# attack_board.net
KiCad netlist of a schematic drawn in Altium Designer
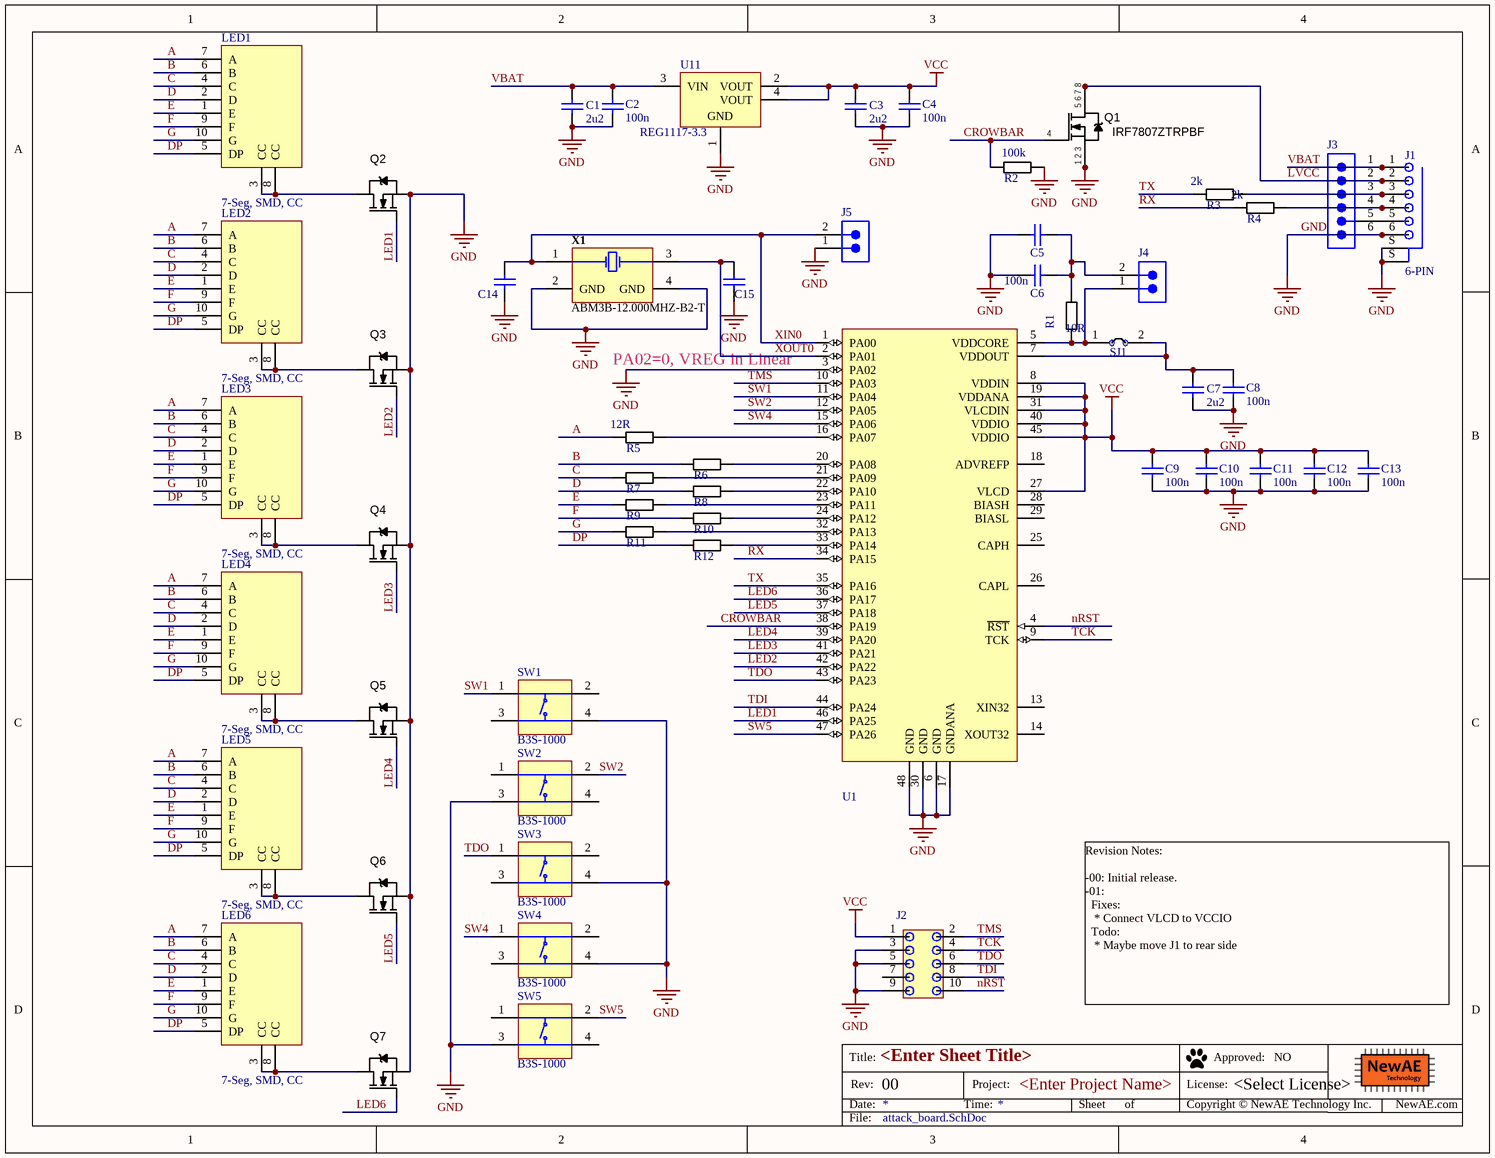
[diagram p0: attack_board.SchDoc]

(export (version "E")
  (design (tool "Eeschema 10.0.6"))
  (components
    (comp (ref "C1")
      (value "2u2")
      (footprint "CAPC0603_M")
      (description "2u2, 0603")
      (fields (field (name "PART NUMBER") "CCHIP-2u2-0603"))
      (libsource (lib "NewAE_AltiumLib") (part "CAP"))
    )
    (comp (ref "C2")
      (value "100n")
      (footprint "CAPC0603_M")
      (description "100n, 0603")
      (fields (field (name "PART NUMBER") "CCHIP-100n-0603"))
      (libsource (lib "NewAE_AltiumLib") (part "CAP"))
    )
    (comp (ref "C3")
      (value "2u2")
      (footprint "CAPC0603_M")
      (description "2u2, 0603")
      (fields (field (name "PART NUMBER") "CCHIP-2u2-0603"))
      (libsource (lib "NewAE_AltiumLib") (part "CAP"))
    )
    (comp (ref "C4")
      (value "100n")
      (footprint "CAPC0603_M")
      (description "100n, 0603")
      (fields (field (name "PART NUMBER") "CCHIP-100n-0603"))
      (libsource (lib "NewAE_AltiumLib") (part "CAP"))
    )
    (comp (ref "C5")
      (value "2u2")
      (footprint "CAPC0603_M")
      (description "2u2, 0603")
      (fields (field (name "PART NUMBER") "CCHIP-2u2-0603"))
      (libsource (lib "NewAE_AltiumLib") (part "CAP"))
    )
    (comp (ref "C6")
      (value "100n")
      (footprint "CAPC0603_M")
      (description "100n, 0603")
      (fields (field (name "PART NUMBER") "CCHIP-100n-0603"))
      (libsource (lib "NewAE_AltiumLib") (part "CAP"))
    )
    (comp (ref "C7")
      (value "2u2")
      (footprint "CAPC0603_M")
      (description "2u2, 0603")
      (fields (field (name "PART NUMBER") "CCHIP-2u2-0603"))
      (libsource (lib "NewAE_AltiumLib") (part "CAP"))
    )
    (comp (ref "C8")
      (value "100n")
      (footprint "CAPC0603_M")
      (description "100n, 0603")
      (fields (field (name "PART NUMBER") "CCHIP-100n-0603"))
      (libsource (lib "NewAE_AltiumLib") (part "CAP"))
    )
    (comp (ref "C9")
      (value "100n")
      (footprint "CAPC0603_M")
      (description "100n, 0603")
      (fields (field (name "PART NUMBER") "CCHIP-100n-0603"))
      (libsource (lib "NewAE_AltiumLib") (part "CAP"))
    )
    (comp (ref "C10")
      (value "100n")
      (footprint "CAPC0603_M")
      (description "100n, 0603")
      (fields (field (name "PART NUMBER") "CCHIP-100n-0603"))
      (libsource (lib "NewAE_AltiumLib") (part "CAP"))
    )
    (comp (ref "C11")
      (value "100n")
      (footprint "CAPC0603_M")
      (description "100n, 0603")
      (fields (field (name "PART NUMBER") "CCHIP-100n-0603"))
      (libsource (lib "NewAE_AltiumLib") (part "CAP"))
    )
    (comp (ref "C12")
      (value "100n")
      (footprint "CAPC0603_M")
      (description "100n, 0603")
      (fields (field (name "PART NUMBER") "CCHIP-100n-0603"))
      (libsource (lib "NewAE_AltiumLib") (part "CAP"))
    )
    (comp (ref "C13")
      (value "100n")
      (footprint "CAPC0603_M")
      (description "100n, 0603")
      (fields (field (name "PART NUMBER") "CCHIP-100n-0603"))
      (libsource (lib "NewAE_AltiumLib") (part "CAP"))
    )
    (comp (ref "C14")
      (value "18p")
      (footprint "CAPC0402_M")
      (description "18p, 0402")
      (fields (field (name "PART NUMBER") "CCHIP-18p-0402"))
      (libsource (lib "NewAE_AltiumLib") (part "CAP"))
    )
    (comp (ref "C15")
      (value "18p")
      (footprint "CAPC0402_M")
      (description "18p, 0402")
      (fields (field (name "PART NUMBER") "CCHIP-18p-0402"))
      (libsource (lib "NewAE_AltiumLib") (part "CAP"))
    )
    (comp (ref "J1")
      (value "6-PIN")
      (footprint "10114828-10106LF")
      (description "1.25MM, 6POS, VERT SMD")
      (fields (field (name "PART NUMBER") "10114828-10106LF"))
      (libsource (lib "NewAE_AltiumLib") (part "CON6_2MNT"))
    )
    (comp (ref "J2")
      (value "1296-T10")
      (footprint "1296-T10")
      (description "Header, 10-pin, SMD, 0.05\"")
      (libsource (lib "NewAE_AltiumLib") (part "CON10_2ROW"))
    )
    (comp (ref "J3")
      (value "~")
      (footprint "SMTC-TSW-106-08-X-S-RA")
      (fields (field (name "PARTNUMBER") "TSW-106-08-T-S-RA") (field (name "MANUFACTURER") "Samtec"))
      (libsource (lib "Altium Content Vault") (part "CMP-1024-00388-1"))
    )
    (comp (ref "J4")
      (value "~")
      (footprint "SMTC-DW-02-16-X-S-200")
      (fields (field (name "PARTNUMBER") "DW-02-16-G-S-200") (field (name "MANUFACTURER") "Samtec"))
      (libsource (lib "Altium Content Vault") (part "CMP-1024-00001-1"))
    )
    (comp (ref "J5")
      (value "~")
      (footprint "SMTC-DW-02-16-X-S-200")
      (fields (field (name "PARTNUMBER") "DW-02-16-G-S-200") (field (name "MANUFACTURER") "Samtec"))
      (libsource (lib "Altium Content Vault") (part "CMP-1024-00001-1"))
    )
    (comp (ref "LED1")
      (value "7-Seg, SMD, CC")
      (description "7-Seg, CC")
      (libsource (lib "NewAE_AltiumLib") (part "ACSC03"))
    )
    (comp (ref "LED2")
      (value "7-Seg, SMD, CC")
      (description "7-Seg, CC")
      (libsource (lib "NewAE_AltiumLib") (part "ACSC03"))
    )
    (comp (ref "LED3")
      (value "7-Seg, SMD, CC")
      (description "7-Seg, CC")
      (libsource (lib "NewAE_AltiumLib") (part "ACSC03"))
    )
    (comp (ref "LED4")
      (value "7-Seg, SMD, CC")
      (description "7-Seg, CC")
      (libsource (lib "NewAE_AltiumLib") (part "ACSC03"))
    )
    (comp (ref "LED5")
      (value "7-Seg, SMD, CC")
      (description "7-Seg, CC")
      (libsource (lib "NewAE_AltiumLib") (part "ACSC03"))
    )
    (comp (ref "LED6")
      (value "7-Seg, SMD, CC")
      (description "7-Seg, CC")
      (libsource (lib "NewAE_AltiumLib") (part "ACSC03"))
    )
    (comp (ref "Q1")
      (value "IRF7807ZTRPBF")
      (footprint "SOIC8_NARROW")
      (description "MOSFET, N-Channel, 8-SOIC, Logic Level")
      (libsource (lib "NewAE_AltiumLib") (part "MOSFET_NCH_8SOIC"))
    )
    (comp (ref "Q2")
      (value "IRLML2502")
      (footprint "SOT95P245X110-3M")
      (description "MOSFET, N-Channel, SOT23, Logic Level")
      (libsource (lib "NewAE_AltiumLib") (part "MOSFET_N_GSD"))
    )
    (comp (ref "Q3")
      (value "IRLML2502")
      (footprint "SOT95P245X110-3M")
      (description "MOSFET, N-Channel, SOT23, Logic Level")
      (libsource (lib "NewAE_AltiumLib") (part "MOSFET_N_GSD"))
    )
    (comp (ref "Q4")
      (value "IRLML2502")
      (footprint "SOT95P245X110-3M")
      (description "MOSFET, N-Channel, SOT23, Logic Level")
      (libsource (lib "NewAE_AltiumLib") (part "MOSFET_N_GSD"))
    )
    (comp (ref "Q5")
      (value "IRLML2502")
      (footprint "SOT95P245X110-3M")
      (description "MOSFET, N-Channel, SOT23, Logic Level")
      (libsource (lib "NewAE_AltiumLib") (part "MOSFET_N_GSD"))
    )
    (comp (ref "Q6")
      (value "IRLML2502")
      (footprint "SOT95P245X110-3M")
      (description "MOSFET, N-Channel, SOT23, Logic Level")
      (libsource (lib "NewAE_AltiumLib") (part "MOSFET_N_GSD"))
    )
    (comp (ref "Q7")
      (value "IRLML2502")
      (footprint "SOT95P245X110-3M")
      (description "MOSFET, N-Channel, SOT23, Logic Level")
      (libsource (lib "NewAE_AltiumLib") (part "MOSFET_N_GSD"))
    )
    (comp (ref "R1")
      (value "10R")
      (footprint "RESC1608X55N")
      (description "10R res, 0603, 1%, 1/10W")
      (fields (field (name "PART NUMBER") "RCHIP-10R-0603") (field (name "TOLERANCE") "1%"))
      (libsource (lib "") (part "RES-EU_1"))
    )
    (comp (ref "R2")
      (value "100k")
      (footprint "RESC1608X55N")
      (description "100k res, 0603, 1%, 1/10W")
      (fields (field (name "PART NUMBER") "RCHIP-100K-0603") (field (name "TOLERANCE") "1%"))
      (libsource (lib "NewAE_AltiumLib") (part "RES-EU"))
    )
    (comp (ref "R3")
      (value "2k")
      (footprint "RESC1608X55N")
      (description "2k res, 0603, 1%, 1/10W")
      (fields (field (name "PART NUMBER") "RCHIP-2K-0603") (field (name "TOLERANCE") "1%"))
      (libsource (lib "NewAE_AltiumLib") (part "RES-EU"))
    )
    (comp (ref "R4")
      (value "2k")
      (footprint "RESC1608X55N")
      (description "2k res, 0603, 1%, 1/10W")
      (fields (field (name "PART NUMBER") "RCHIP-2K-0603") (field (name "TOLERANCE") "1%"))
      (libsource (lib "NewAE_AltiumLib") (part "RES-EU"))
    )
    (comp (ref "R5")
      (value "12R")
      (footprint "RESC1608X55N")
      (description "12R res, 0603, 1%, 1/10W")
      (fields (field (name "PART NUMBER") "RCHIP-12R-0603") (field (name "TOLERANCE") "1%"))
      (libsource (lib "NewAE_AltiumLib") (part "RES-EU"))
    )
    (comp (ref "R6")
      (value "12R")
      (footprint "RESC1608X55N")
      (description "12R res, 0603, 1%, 1/10W")
      (fields (field (name "PART NUMBER") "RCHIP-12R-0603") (field (name "TOLERANCE") "1%"))
      (libsource (lib "NewAE_AltiumLib") (part "RES-EU"))
    )
    (comp (ref "R7")
      (value "12R")
      (footprint "RESC1608X55N")
      (description "12R res, 0603, 1%, 1/10W")
      (fields (field (name "PART NUMBER") "RCHIP-12R-0603") (field (name "TOLERANCE") "1%"))
      (libsource (lib "NewAE_AltiumLib") (part "RES-EU"))
    )
    (comp (ref "R8")
      (value "12R")
      (footprint "RESC1608X55N")
      (description "12R res, 0603, 1%, 1/10W")
      (fields (field (name "PART NUMBER") "RCHIP-12R-0603") (field (name "TOLERANCE") "1%"))
      (libsource (lib "NewAE_AltiumLib") (part "RES-EU"))
    )
    (comp (ref "R9")
      (value "12R")
      (footprint "RESC1608X55N")
      (description "12R res, 0603, 1%, 1/10W")
      (fields (field (name "PART NUMBER") "RCHIP-12R-0603") (field (name "TOLERANCE") "1%"))
      (libsource (lib "NewAE_AltiumLib") (part "RES-EU"))
    )
    (comp (ref "R10")
      (value "12R")
      (footprint "RESC1608X55N")
      (description "12R res, 0603, 1%, 1/10W")
      (fields (field (name "PART NUMBER") "RCHIP-12R-0603") (field (name "TOLERANCE") "1%"))
      (libsource (lib "NewAE_AltiumLib") (part "RES-EU"))
    )
    (comp (ref "R11")
      (value "12R")
      (footprint "RESC1608X55N")
      (description "12R res, 0603, 1%, 1/10W")
      (fields (field (name "PART NUMBER") "RCHIP-12R-0603") (field (name "TOLERANCE") "1%"))
      (libsource (lib "NewAE_AltiumLib") (part "RES-EU"))
    )
    (comp (ref "R12")
      (value "12R")
      (footprint "RESC1608X55N")
      (description "12R res, 0603, 1%, 1/10W")
      (fields (field (name "PART NUMBER") "RCHIP-12R-0603") (field (name "TOLERANCE") "1%"))
      (libsource (lib "NewAE_AltiumLib") (part "RES-EU"))
    )
    (comp (ref "SJ1")
      (value "NC")
      (footprint "SJ_2S_NC")
      (description "Solder Jumper, NC")
      (fields (field (name "PART NUMBER") "SJ_2S"))
      (libsource (lib "NewAE_AltiumLib") (part "SJ_2S"))
    )
    (comp (ref "SW1")
      (value "B3S-1000")
      (footprint "OMRON-B3S-1000-4_V")
      (description "Sealed Tactile Switch, SPST-NO, 3 to 24 V, -25 to 70 degC, 4-Pin SMD, RoHS, Bulk")
      (fields (field (name "MANUFACTURER") "Omron"))
      (libsource (lib "Altium Content Vault") (part "SW-SPST-4_A"))
    )
    (comp (ref "SW2")
      (value "B3S-1000")
      (footprint "OMRON-B3S-1000-4_V")
      (description "Sealed Tactile Switch, SPST-NO, 3 to 24 V, -25 to 70 degC, 4-Pin SMD, RoHS, Bulk")
      (fields (field (name "MANUFACTURER") "Omron"))
      (libsource (lib "Altium Content Vault") (part "SW-SPST-4_A"))
    )
    (comp (ref "SW3")
      (value "B3S-1000")
      (footprint "OMRON-B3S-1000-4_V")
      (description "Sealed Tactile Switch, SPST-NO, 3 to 24 V, -25 to 70 degC, 4-Pin SMD, RoHS, Bulk")
      (fields (field (name "MANUFACTURER") "Omron"))
      (libsource (lib "Altium Content Vault") (part "CMP-1677-00001-4"))
    )
    (comp (ref "SW4")
      (value "B3S-1000")
      (footprint "OMRON-B3S-1000-4_V")
      (description "Sealed Tactile Switch, SPST-NO, 3 to 24 V, -25 to 70 degC, 4-Pin SMD, RoHS, Bulk")
      (fields (field (name "MANUFACTURER") "Omron"))
      (libsource (lib "Altium Content Vault") (part "CMP-1677-00001-4"))
    )
    (comp (ref "SW5")
      (value "B3S-1000")
      (footprint "OMRON-B3S-1000-4_V")
      (description "Sealed Tactile Switch, SPST-NO, 3 to 24 V, -25 to 70 degC, 4-Pin SMD, RoHS, Bulk")
      (fields (field (name "MANUFACTURER") "Omron"))
      (libsource (lib "Altium Content Vault") (part "CMP-1677-00001-4"))
    )
    (comp (ref "U1")
      (value "ATSAM4LC2AA-AU")
      (footprint "TSQFP50P900X900X120-48N")
      (description "Atmel, SAM4L, 48-TQFP")
      (libsource (lib "NewAE_AltiumLib") (part "ATSAM4LxxA"))
    )
    (comp (ref "U11")
      (value "REG1117-3.3")
      (footprint "TI-DCY4_M")
      (fields (field (name "MANUFACTURER") "Texas Instruments"))
      (libsource (lib "Altium Content Vault") (part "CMP-0395-00549-1"))
    )
    (comp (ref "X1")
      (value "ABM3B-12.000MHZ-B2-T")
      (footprint "ABRA-ABM3B-4_V")
      (description "Ceramic SMD Crystal, 12 MHz, +/- 20 ppm, 70 Ohm, -20 to 70 degC, 4-Pin SMD, RoHS, Tape and Reel")
      (libsource (lib "Altium Content Vault") (part "XTAL-1-3-4"))
    )
  )
  (nets
    (net (code "1") (name "/A") (class "Default")
      (node (ref "LED1") (pin "7") (pinfunction "A_7") (pintype "passive"))
      (node (ref "LED2") (pin "7") (pinfunction "A_7") (pintype "passive"))
      (node (ref "LED3") (pin "7") (pinfunction "A_7") (pintype "passive"))
      (node (ref "LED4") (pin "7") (pinfunction "A_7") (pintype "passive"))
      (node (ref "LED5") (pin "7") (pinfunction "A_7") (pintype "passive"))
      (node (ref "LED6") (pin "7") (pinfunction "A_7") (pintype "passive"))
      (node (ref "R5") (pin "1") (pinfunction "1_1") (pintype "passive"))
    )
    (net (code "2") (name "/B") (class "Default")
      (node (ref "LED1") (pin "6") (pinfunction "B_6") (pintype "passive"))
      (node (ref "LED2") (pin "6") (pinfunction "B_6") (pintype "passive"))
      (node (ref "LED3") (pin "6") (pinfunction "B_6") (pintype "passive"))
      (node (ref "LED4") (pin "6") (pinfunction "B_6") (pintype "passive"))
      (node (ref "LED5") (pin "6") (pinfunction "B_6") (pintype "passive"))
      (node (ref "LED6") (pin "6") (pinfunction "B_6") (pintype "passive"))
      (node (ref "R6") (pin "1") (pinfunction "1_1") (pintype "passive"))
    )
    (net (code "3") (name "/C") (class "Default")
      (node (ref "LED1") (pin "4") (pinfunction "C_4") (pintype "passive"))
      (node (ref "LED2") (pin "4") (pinfunction "C_4") (pintype "passive"))
      (node (ref "LED3") (pin "4") (pinfunction "C_4") (pintype "passive"))
      (node (ref "LED4") (pin "4") (pinfunction "C_4") (pintype "passive"))
      (node (ref "LED5") (pin "4") (pinfunction "C_4") (pintype "passive"))
      (node (ref "LED6") (pin "4") (pinfunction "C_4") (pintype "passive"))
      (node (ref "R7") (pin "1") (pinfunction "1_1") (pintype "passive"))
    )
    (net (code "4") (name "/CROWBAR") (class "Default")
      (node (ref "Q1") (pin "4") (pinfunction "G_4") (pintype "passive"))
      (node (ref "R2") (pin "1") (pinfunction "1_1") (pintype "passive"))
      (node (ref "U1") (pin "38") (pinfunction "PA19_38") (pintype "bidirectional"))
    )
    (net (code "5") (name "/D") (class "Default")
      (node (ref "LED1") (pin "2") (pinfunction "D_2") (pintype "passive"))
      (node (ref "LED2") (pin "2") (pinfunction "D_2") (pintype "passive"))
      (node (ref "LED3") (pin "2") (pinfunction "D_2") (pintype "passive"))
      (node (ref "LED4") (pin "2") (pinfunction "D_2") (pintype "passive"))
      (node (ref "LED5") (pin "2") (pinfunction "D_2") (pintype "passive"))
      (node (ref "LED6") (pin "2") (pinfunction "D_2") (pintype "passive"))
      (node (ref "R8") (pin "1") (pinfunction "1_1") (pintype "passive"))
    )
    (net (code "6") (name "/DP") (class "Default")
      (node (ref "LED1") (pin "5") (pinfunction "DP_5") (pintype "passive"))
      (node (ref "LED2") (pin "5") (pinfunction "DP_5") (pintype "passive"))
      (node (ref "LED3") (pin "5") (pinfunction "DP_5") (pintype "passive"))
      (node (ref "LED4") (pin "5") (pinfunction "DP_5") (pintype "passive"))
      (node (ref "LED5") (pin "5") (pinfunction "DP_5") (pintype "passive"))
      (node (ref "LED6") (pin "5") (pinfunction "DP_5") (pintype "passive"))
      (node (ref "R12") (pin "1") (pinfunction "1_1") (pintype "passive"))
    )
    (net (code "7") (name "/E") (class "Default")
      (node (ref "LED1") (pin "1") (pinfunction "E_1") (pintype "passive"))
      (node (ref "LED2") (pin "1") (pinfunction "E_1") (pintype "passive"))
      (node (ref "LED3") (pin "1") (pinfunction "E_1") (pintype "passive"))
      (node (ref "LED4") (pin "1") (pinfunction "E_1") (pintype "passive"))
      (node (ref "LED5") (pin "1") (pinfunction "E_1") (pintype "passive"))
      (node (ref "LED6") (pin "1") (pinfunction "E_1") (pintype "passive"))
      (node (ref "R9") (pin "1") (pinfunction "1_1") (pintype "passive"))
    )
    (net (code "8") (name "/F") (class "Default")
      (node (ref "LED1") (pin "9") (pinfunction "F_9") (pintype "passive"))
      (node (ref "LED2") (pin "9") (pinfunction "F_9") (pintype "passive"))
      (node (ref "LED3") (pin "9") (pinfunction "F_9") (pintype "passive"))
      (node (ref "LED4") (pin "9") (pinfunction "F_9") (pintype "passive"))
      (node (ref "LED5") (pin "9") (pinfunction "F_9") (pintype "passive"))
      (node (ref "LED6") (pin "9") (pinfunction "F_9") (pintype "passive"))
      (node (ref "R10") (pin "1") (pinfunction "1_1") (pintype "passive"))
    )
    (net (code "9") (name "/G") (class "Default")
      (node (ref "LED1") (pin "10") (pinfunction "G_10") (pintype "passive"))
      (node (ref "LED2") (pin "10") (pinfunction "G_10") (pintype "passive"))
      (node (ref "LED3") (pin "10") (pinfunction "G_10") (pintype "passive"))
      (node (ref "LED4") (pin "10") (pinfunction "G_10") (pintype "passive"))
      (node (ref "LED5") (pin "10") (pinfunction "G_10") (pintype "passive"))
      (node (ref "LED6") (pin "10") (pinfunction "G_10") (pintype "passive"))
      (node (ref "R11") (pin "1") (pinfunction "1_1") (pintype "passive"))
    )
    (net (code "10") (name "/LED1") (class "Default")
      (node (ref "Q2") (pin "1") (pinfunction "G_1") (pintype "passive"))
      (node (ref "U1") (pin "46") (pinfunction "PA25_46") (pintype "bidirectional"))
    )
    (net (code "11") (name "/LED2") (class "Default")
      (node (ref "Q3") (pin "1") (pinfunction "G_1") (pintype "passive"))
      (node (ref "U1") (pin "42") (pinfunction "PA22_42") (pintype "bidirectional"))
    )
    (net (code "12") (name "/LED3") (class "Default")
      (node (ref "Q4") (pin "1") (pinfunction "G_1") (pintype "passive"))
      (node (ref "U1") (pin "41") (pinfunction "PA21_41") (pintype "bidirectional"))
    )
    (net (code "13") (name "/LED4") (class "Default")
      (node (ref "Q5") (pin "1") (pinfunction "G_1") (pintype "passive"))
      (node (ref "U1") (pin "39") (pinfunction "PA20_39") (pintype "bidirectional"))
    )
    (net (code "14") (name "/LED5") (class "Default")
      (node (ref "Q6") (pin "1") (pinfunction "G_1") (pintype "passive"))
      (node (ref "U1") (pin "37") (pinfunction "PA18_37") (pintype "bidirectional"))
    )
    (net (code "15") (name "/LED6") (class "Default")
      (node (ref "Q7") (pin "1") (pinfunction "G_1") (pintype "passive"))
      (node (ref "U1") (pin "36") (pinfunction "PA17_36") (pintype "bidirectional"))
    )
    (net (code "16") (name "/LVCC") (class "Default")
      (node (ref "J1") (pin "2") (pinfunction "2_2") (pintype "passive"))
      (node (ref "J3") (pin "2") (pinfunction "2_2") (pintype "passive"))
      (node (ref "Q1") (pin "5") (pinfunction "5,6,7,8_5") (pintype "passive"))
      (node (ref "Q1") (pin "6") (pinfunction "D_6") (pintype "passive"))
      (node (ref "Q1") (pin "7") (pinfunction "D_7") (pintype "passive"))
      (node (ref "Q1") (pin "8") (pinfunction "D_8") (pintype "passive"))
    )
    (net (code "17") (name "/RX") (class "Default")
      (node (ref "R4") (pin "1") (pinfunction "1_1") (pintype "passive"))
      (node (ref "U1") (pin "34") (pinfunction "PA15_34") (pintype "bidirectional"))
    )
    (net (code "18") (name "/SW1") (class "Default")
      (node (ref "SW1") (pin "1") (pinfunction "1_1") (pintype "passive"))
      (node (ref "U1") (pin "11") (pinfunction "PA04_11") (pintype "bidirectional"))
    )
    (net (code "19") (name "/SW2") (class "Default")
      (node (ref "SW2") (pin "2") (pinfunction "2_2") (pintype "passive"))
      (node (ref "U1") (pin "12") (pinfunction "PA05_12") (pintype "bidirectional"))
    )
    (net (code "20") (name "/SW4") (class "Default")
      (node (ref "SW4") (pin "1") (pinfunction "1_1") (pintype "passive"))
      (node (ref "U1") (pin "15") (pinfunction "PA06_15") (pintype "bidirectional"))
    )
    (net (code "21") (name "/SW5") (class "Default")
      (node (ref "SW5") (pin "2") (pinfunction "2_2") (pintype "passive"))
      (node (ref "U1") (pin "47") (pinfunction "PA26_47") (pintype "bidirectional"))
    )
    (net (code "22") (name "/TCK") (class "Default")
      (node (ref "J2") (pin "4") (pinfunction "4_4") (pintype "passive"))
      (node (ref "U1") (pin "9") (pinfunction "TCK_9") (pintype "bidirectional"))
    )
    (net (code "23") (name "/TDI") (class "Default")
      (node (ref "J2") (pin "8") (pinfunction "8_8") (pintype "passive"))
      (node (ref "U1") (pin "44") (pinfunction "PA24_44") (pintype "bidirectional"))
    )
    (net (code "24") (name "/TDO") (class "Default")
      (node (ref "J2") (pin "6") (pinfunction "6_6") (pintype "passive"))
      (node (ref "SW3") (pin "1") (pinfunction "1_1") (pintype "passive"))
      (node (ref "U1") (pin "43") (pinfunction "PA23_43") (pintype "bidirectional"))
    )
    (net (code "25") (name "/TMS") (class "Default")
      (node (ref "J2") (pin "2") (pinfunction "2_2") (pintype "passive"))
      (node (ref "U1") (pin "10") (pinfunction "PA03_10") (pintype "bidirectional"))
    )
    (net (code "26") (name "/TX") (class "Default")
      (node (ref "R3") (pin "1") (pinfunction "1_1") (pintype "passive"))
      (node (ref "U1") (pin "35") (pinfunction "PA16_35") (pintype "bidirectional"))
    )
    (net (code "27") (name "/VBAT") (class "Default")
      (node (ref "C1") (pin "1") (pinfunction "1_1") (pintype "passive"))
      (node (ref "C2") (pin "2") (pinfunction "2_2") (pintype "passive"))
      (node (ref "J1") (pin "1") (pinfunction "1_1") (pintype "passive"))
      (node (ref "J3") (pin "1") (pinfunction "1_1") (pintype "passive"))
      (node (ref "U11") (pin "3") (pinfunction "VIN_3") (pintype "power_in"))
    )
    (net (code "28") (name "/XIN0") (class "Default")
      (node (ref "C14") (pin "2") (pinfunction "2_2") (pintype "passive"))
      (node (ref "J5") (pin "2") (pinfunction "2_2") (pintype "passive"))
      (node (ref "U1") (pin "1") (pinfunction "PA00_1") (pintype "bidirectional"))
      (node (ref "X1") (pin "1") (pinfunction "X1_1") (pintype "passive"))
    )
    (net (code "29") (name "/XOUT0") (class "Default")
      (node (ref "C15") (pin "2") (pinfunction "2_2") (pintype "passive"))
      (node (ref "U1") (pin "2") (pinfunction "PA01_2") (pintype "bidirectional"))
      (node (ref "X1") (pin "3") (pinfunction "X2_3") (pintype "passive"))
    )
    (net (code "30") (name "/nRST") (class "Default")
      (node (ref "J2") (pin "10") (pinfunction "10_10") (pintype "passive"))
      (node (ref "U1") (pin "4") (pinfunction "~{RST}_4") (pintype "input"))
    )
    (net (code "31") (name "GND") (class "Default")
      (node (ref "C1") (pin "2") (pinfunction "2_2") (pintype "passive"))
      (node (ref "C10") (pin "1") (pinfunction "1_1") (pintype "passive"))
      (node (ref "C11") (pin "1") (pinfunction "1_1") (pintype "passive"))
      (node (ref "C12") (pin "1") (pinfunction "1_1") (pintype "passive"))
      (node (ref "C13") (pin "1") (pinfunction "1_1") (pintype "passive"))
      (node (ref "C14") (pin "1") (pinfunction "1_1") (pintype "passive"))
      (node (ref "C15") (pin "1") (pinfunction "1_1") (pintype "passive"))
      (node (ref "C2") (pin "1") (pinfunction "1_1") (pintype "passive"))
      (node (ref "C3") (pin "2") (pinfunction "2_2") (pintype "passive"))
      (node (ref "C4") (pin "1") (pinfunction "1_1") (pintype "passive"))
      (node (ref "C5") (pin "1") (pinfunction "1_1") (pintype "passive"))
      (node (ref "C6") (pin "1") (pinfunction "1_1") (pintype "passive"))
      (node (ref "C7") (pin "2") (pinfunction "2_2") (pintype "passive"))
      (node (ref "C8") (pin "1") (pinfunction "1_1") (pintype "passive"))
      (node (ref "C9") (pin "1") (pinfunction "1_1") (pintype "passive"))
      (node (ref "J1") (pin "6") (pinfunction "6_6") (pintype "passive"))
      (node (ref "J1") (pin "S") (pinfunction "MNT_S") (pintype "passive"))
      (node (ref "J2") (pin "3") (pinfunction "3_3") (pintype "passive"))
      (node (ref "J2") (pin "5") (pinfunction "5_5") (pintype "passive"))
      (node (ref "J2") (pin "9") (pinfunction "9_9") (pintype "passive"))
      (node (ref "J3") (pin "6") (pinfunction "6_6") (pintype "passive"))
      (node (ref "J5") (pin "1") (pinfunction "1_1") (pintype "passive"))
      (node (ref "Q1") (pin "1") (pinfunction "1,2,3_1") (pintype "passive"))
      (node (ref "Q1") (pin "2") (pinfunction "S_2") (pintype "passive"))
      (node (ref "Q1") (pin "3") (pinfunction "S_3") (pintype "passive"))
      (node (ref "Q2") (pin "2") (pinfunction "S_2") (pintype "passive"))
      (node (ref "Q3") (pin "2") (pinfunction "S_2") (pintype "passive"))
      (node (ref "Q4") (pin "2") (pinfunction "S_2") (pintype "passive"))
      (node (ref "Q5") (pin "2") (pinfunction "S_2") (pintype "passive"))
      (node (ref "Q6") (pin "2") (pinfunction "S_2") (pintype "passive"))
      (node (ref "Q7") (pin "2") (pinfunction "S_2") (pintype "passive"))
      (node (ref "R2") (pin "2") (pinfunction "2_2") (pintype "passive"))
      (node (ref "SW1") (pin "4") (pinfunction "4_4") (pintype "passive"))
      (node (ref "SW2") (pin "3") (pinfunction "3_3") (pintype "passive"))
      (node (ref "SW3") (pin "4") (pinfunction "4_4") (pintype "passive"))
      (node (ref "SW4") (pin "4") (pinfunction "4_4") (pintype "passive"))
      (node (ref "SW5") (pin "3") (pinfunction "3_3") (pintype "passive"))
      (node (ref "U1") (pin "17") (pinfunction "GNDANA_17") (pintype "power_in"))
      (node (ref "U1") (pin "3") (pinfunction "PA02_3") (pintype "bidirectional"))
      (node (ref "U1") (pin "30") (pinfunction "GND_30") (pintype "power_in"))
      (node (ref "U1") (pin "48") (pinfunction "GND_48") (pintype "power_in"))
      (node (ref "U1") (pin "6") (pinfunction "GND_6") (pintype "power_in"))
      (node (ref "U11") (pin "1") (pinfunction "GND_1") (pintype "power_in"))
      (node (ref "X1") (pin "2") (pinfunction "GND_2") (pintype "power_in"))
      (node (ref "X1") (pin "4") (pinfunction "GND_4") (pintype "power_in"))
    )
    (net (code "32") (name "Net-(C5-Pad2)") (class "Default")
      (node (ref "C5") (pin "2") (pinfunction "2_2") (pintype "passive"))
      (node (ref "C6") (pin "2") (pinfunction "2_2") (pintype "passive"))
      (node (ref "J4") (pin "2") (pinfunction "2_2") (pintype "passive"))
      (node (ref "R1") (pin "1") (pinfunction "1_1") (pintype "passive"))
    )
    (net (code "33") (name "Net-(J1-Pad3)") (class "Default")
      (node (ref "J1") (pin "3") (pinfunction "3_3") (pintype "passive"))
      (node (ref "J3") (pin "3") (pinfunction "3_3") (pintype "passive"))
      (node (ref "R3") (pin "2") (pinfunction "2_2") (pintype "passive"))
    )
    (net (code "34") (name "Net-(J1-Pad4)") (class "Default")
      (node (ref "J1") (pin "4") (pinfunction "4_4") (pintype "passive"))
      (node (ref "J3") (pin "4") (pinfunction "4_4") (pintype "passive"))
      (node (ref "R4") (pin "2") (pinfunction "2_2") (pintype "passive"))
    )
    (net (code "35") (name "Net-(J1-Pad5)") (class "Default")
      (node (ref "J1") (pin "5") (pinfunction "5_5") (pintype "passive"))
      (node (ref "J3") (pin "5") (pinfunction "5_5") (pintype "passive"))
    )
    (net (code "36") (name "Net-(Q2-D)") (class "Default")
      (node (ref "LED1") (pin "3") (pinfunction "CC_3") (pintype "passive"))
      (node (ref "LED1") (pin "8") (pinfunction "CC_8") (pintype "passive"))
      (node (ref "Q2") (pin "3") (pinfunction "D_3") (pintype "passive"))
    )
    (net (code "37") (name "Net-(Q3-D)") (class "Default")
      (node (ref "LED2") (pin "3") (pinfunction "CC_3") (pintype "passive"))
      (node (ref "LED2") (pin "8") (pinfunction "CC_8") (pintype "passive"))
      (node (ref "Q3") (pin "3") (pinfunction "D_3") (pintype "passive"))
    )
    (net (code "38") (name "Net-(Q4-D)") (class "Default")
      (node (ref "LED3") (pin "3") (pinfunction "CC_3") (pintype "passive"))
      (node (ref "LED3") (pin "8") (pinfunction "CC_8") (pintype "passive"))
      (node (ref "Q4") (pin "3") (pinfunction "D_3") (pintype "passive"))
    )
    (net (code "39") (name "Net-(Q5-D)") (class "Default")
      (node (ref "LED4") (pin "3") (pinfunction "CC_3") (pintype "passive"))
      (node (ref "LED4") (pin "8") (pinfunction "CC_8") (pintype "passive"))
      (node (ref "Q5") (pin "3") (pinfunction "D_3") (pintype "passive"))
    )
    (net (code "40") (name "Net-(Q6-D)") (class "Default")
      (node (ref "LED5") (pin "3") (pinfunction "CC_3") (pintype "passive"))
      (node (ref "LED5") (pin "8") (pinfunction "CC_8") (pintype "passive"))
      (node (ref "Q6") (pin "3") (pinfunction "D_3") (pintype "passive"))
    )
    (net (code "41") (name "Net-(Q7-D)") (class "Default")
      (node (ref "LED6") (pin "3") (pinfunction "CC_3") (pintype "passive"))
      (node (ref "LED6") (pin "8") (pinfunction "CC_8") (pintype "passive"))
      (node (ref "Q7") (pin "3") (pinfunction "D_3") (pintype "passive"))
    )
    (net (code "42") (name "Net-(U1-PA07)") (class "Default")
      (node (ref "R5") (pin "2") (pinfunction "2_2") (pintype "passive"))
      (node (ref "U1") (pin "16") (pinfunction "PA07_16") (pintype "bidirectional"))
    )
    (net (code "43") (name "Net-(U1-PA08)") (class "Default")
      (node (ref "R6") (pin "2") (pinfunction "2_2") (pintype "passive"))
      (node (ref "U1") (pin "20") (pinfunction "PA08_20") (pintype "bidirectional"))
    )
    (net (code "44") (name "Net-(U1-PA09)") (class "Default")
      (node (ref "R7") (pin "2") (pinfunction "2_2") (pintype "passive"))
      (node (ref "U1") (pin "21") (pinfunction "PA09_21") (pintype "bidirectional"))
    )
    (net (code "45") (name "Net-(U1-PA10)") (class "Default")
      (node (ref "R8") (pin "2") (pinfunction "2_2") (pintype "passive"))
      (node (ref "U1") (pin "22") (pinfunction "PA10_22") (pintype "bidirectional"))
    )
    (net (code "46") (name "Net-(U1-PA11)") (class "Default")
      (node (ref "R9") (pin "2") (pinfunction "2_2") (pintype "passive"))
      (node (ref "U1") (pin "23") (pinfunction "PA11_23") (pintype "bidirectional"))
    )
    (net (code "47") (name "Net-(U1-PA12)") (class "Default")
      (node (ref "R10") (pin "2") (pinfunction "2_2") (pintype "passive"))
      (node (ref "U1") (pin "24") (pinfunction "PA12_24") (pintype "bidirectional"))
    )
    (net (code "48") (name "Net-(U1-PA13)") (class "Default")
      (node (ref "R11") (pin "2") (pinfunction "2_2") (pintype "passive"))
      (node (ref "U1") (pin "32") (pinfunction "PA13_32") (pintype "bidirectional"))
    )
    (net (code "49") (name "Net-(U1-PA14)") (class "Default")
      (node (ref "R12") (pin "2") (pinfunction "2_2") (pintype "passive"))
      (node (ref "U1") (pin "33") (pinfunction "PA14_33") (pintype "bidirectional"))
    )
    (net (code "50") (name "Net-(U1-VDDCORE)") (class "Default")
      (node (ref "J4") (pin "1") (pinfunction "1_1") (pintype "passive"))
      (node (ref "R1") (pin "2") (pinfunction "2_2") (pintype "passive"))
      (node (ref "SJ1") (pin "1") (pinfunction "1_1") (pintype "passive"))
      (node (ref "U1") (pin "5") (pinfunction "VDDCORE_5") (pintype "passive"))
    )
    (net (code "51") (name "Net-(U1-VDDOUT)") (class "Default")
      (node (ref "C7") (pin "1") (pinfunction "1_1") (pintype "passive"))
      (node (ref "C8") (pin "2") (pinfunction "2_2") (pintype "passive"))
      (node (ref "SJ1") (pin "2") (pinfunction "2_2") (pintype "passive"))
      (node (ref "U1") (pin "7") (pinfunction "VDDOUT_7") (pintype "passive"))
    )
    (net (code "52") (name "VCC") (class "Default")
      (node (ref "C10") (pin "2") (pinfunction "2_2") (pintype "passive"))
      (node (ref "C11") (pin "2") (pinfunction "2_2") (pintype "passive"))
      (node (ref "C12") (pin "2") (pinfunction "2_2") (pintype "passive"))
      (node (ref "C13") (pin "2") (pinfunction "2_2") (pintype "passive"))
      (node (ref "C3") (pin "1") (pinfunction "1_1") (pintype "passive"))
      (node (ref "C4") (pin "2") (pinfunction "2_2") (pintype "passive"))
      (node (ref "C9") (pin "2") (pinfunction "2_2") (pintype "passive"))
      (node (ref "J2") (pin "1") (pinfunction "1_1") (pintype "passive"))
      (node (ref "U1") (pin "19") (pinfunction "VDDANA_19") (pintype "power_in"))
      (node (ref "U1") (pin "27") (pinfunction "VLCD_27") (pintype "passive"))
      (node (ref "U1") (pin "31") (pinfunction "VLCDIN_31") (pintype "power_in"))
      (node (ref "U1") (pin "40") (pinfunction "VDDIO_40") (pintype "power_in"))
      (node (ref "U1") (pin "45") (pinfunction "VDDIO_45") (pintype "power_in"))
      (node (ref "U1") (pin "8") (pinfunction "VDDIN_8") (pintype "power_in"))
      (node (ref "U11") (pin "2") (pinfunction "VOUT_2") (pintype "power_in"))
      (node (ref "U11") (pin "4") (pinfunction "VOUT_4") (pintype "power_in"))
    )
    (net (code "53") (name "unconnected-(J2-Pad7)") (class "Default")
      (node (ref "J2") (pin "7") (pinfunction "7_7") (pintype "passive"))
    )
    (net (code "54") (name "unconnected-(SW1-Pad2)") (class "Default")
      (node (ref "SW1") (pin "2") (pinfunction "2_2") (pintype "passive"))
    )
    (net (code "55") (name "unconnected-(SW1-Pad3)") (class "Default")
      (node (ref "SW1") (pin "3") (pinfunction "3_3") (pintype "passive"))
    )
    (net (code "56") (name "unconnected-(SW2-Pad1)") (class "Default")
      (node (ref "SW2") (pin "1") (pinfunction "1_1") (pintype "passive"))
    )
    (net (code "57") (name "unconnected-(SW2-Pad4)") (class "Default")
      (node (ref "SW2") (pin "4") (pinfunction "4_4") (pintype "passive"))
    )
    (net (code "58") (name "unconnected-(SW3-Pad2)") (class "Default")
      (node (ref "SW3") (pin "2") (pinfunction "2_2") (pintype "passive"))
    )
    (net (code "59") (name "unconnected-(SW3-Pad3)") (class "Default")
      (node (ref "SW3") (pin "3") (pinfunction "3_3") (pintype "passive"))
    )
    (net (code "60") (name "unconnected-(SW4-Pad2)") (class "Default")
      (node (ref "SW4") (pin "2") (pinfunction "2_2") (pintype "passive"))
    )
    (net (code "61") (name "unconnected-(SW4-Pad3)") (class "Default")
      (node (ref "SW4") (pin "3") (pinfunction "3_3") (pintype "passive"))
    )
    (net (code "62") (name "unconnected-(SW5-Pad1)") (class "Default")
      (node (ref "SW5") (pin "1") (pinfunction "1_1") (pintype "passive"))
    )
    (net (code "63") (name "unconnected-(SW5-Pad4)") (class "Default")
      (node (ref "SW5") (pin "4") (pinfunction "4_4") (pintype "passive"))
    )
    (net (code "64") (name "unconnected-(U1-ADVREFP-Pad18)") (class "Default")
      (node (ref "U1") (pin "18") (pinfunction "ADVREFP_18") (pintype "passive"))
    )
    (net (code "65") (name "unconnected-(U1-BIASH-Pad28)") (class "Default")
      (node (ref "U1") (pin "28") (pinfunction "BIASH_28") (pintype "passive"))
    )
    (net (code "66") (name "unconnected-(U1-BIASL-Pad29)") (class "Default")
      (node (ref "U1") (pin "29") (pinfunction "BIASL_29") (pintype "passive"))
    )
    (net (code "67") (name "unconnected-(U1-CAPH-Pad25)") (class "Default")
      (node (ref "U1") (pin "25") (pinfunction "CAPH_25") (pintype "passive"))
    )
    (net (code "68") (name "unconnected-(U1-CAPL-Pad26)") (class "Default")
      (node (ref "U1") (pin "26") (pinfunction "CAPL_26") (pintype "passive"))
    )
    (net (code "69") (name "unconnected-(U1-XIN32-Pad13)") (class "Default")
      (node (ref "U1") (pin "13") (pinfunction "XIN32_13") (pintype "passive"))
    )
    (net (code "70") (name "unconnected-(U1-XOUT32-Pad14)") (class "Default")
      (node (ref "U1") (pin "14") (pinfunction "XOUT32_14") (pintype "passive"))
    )
  )
)
